# jlink_to_tag.net
KiCad netlist of a schematic drawn in EAGLE
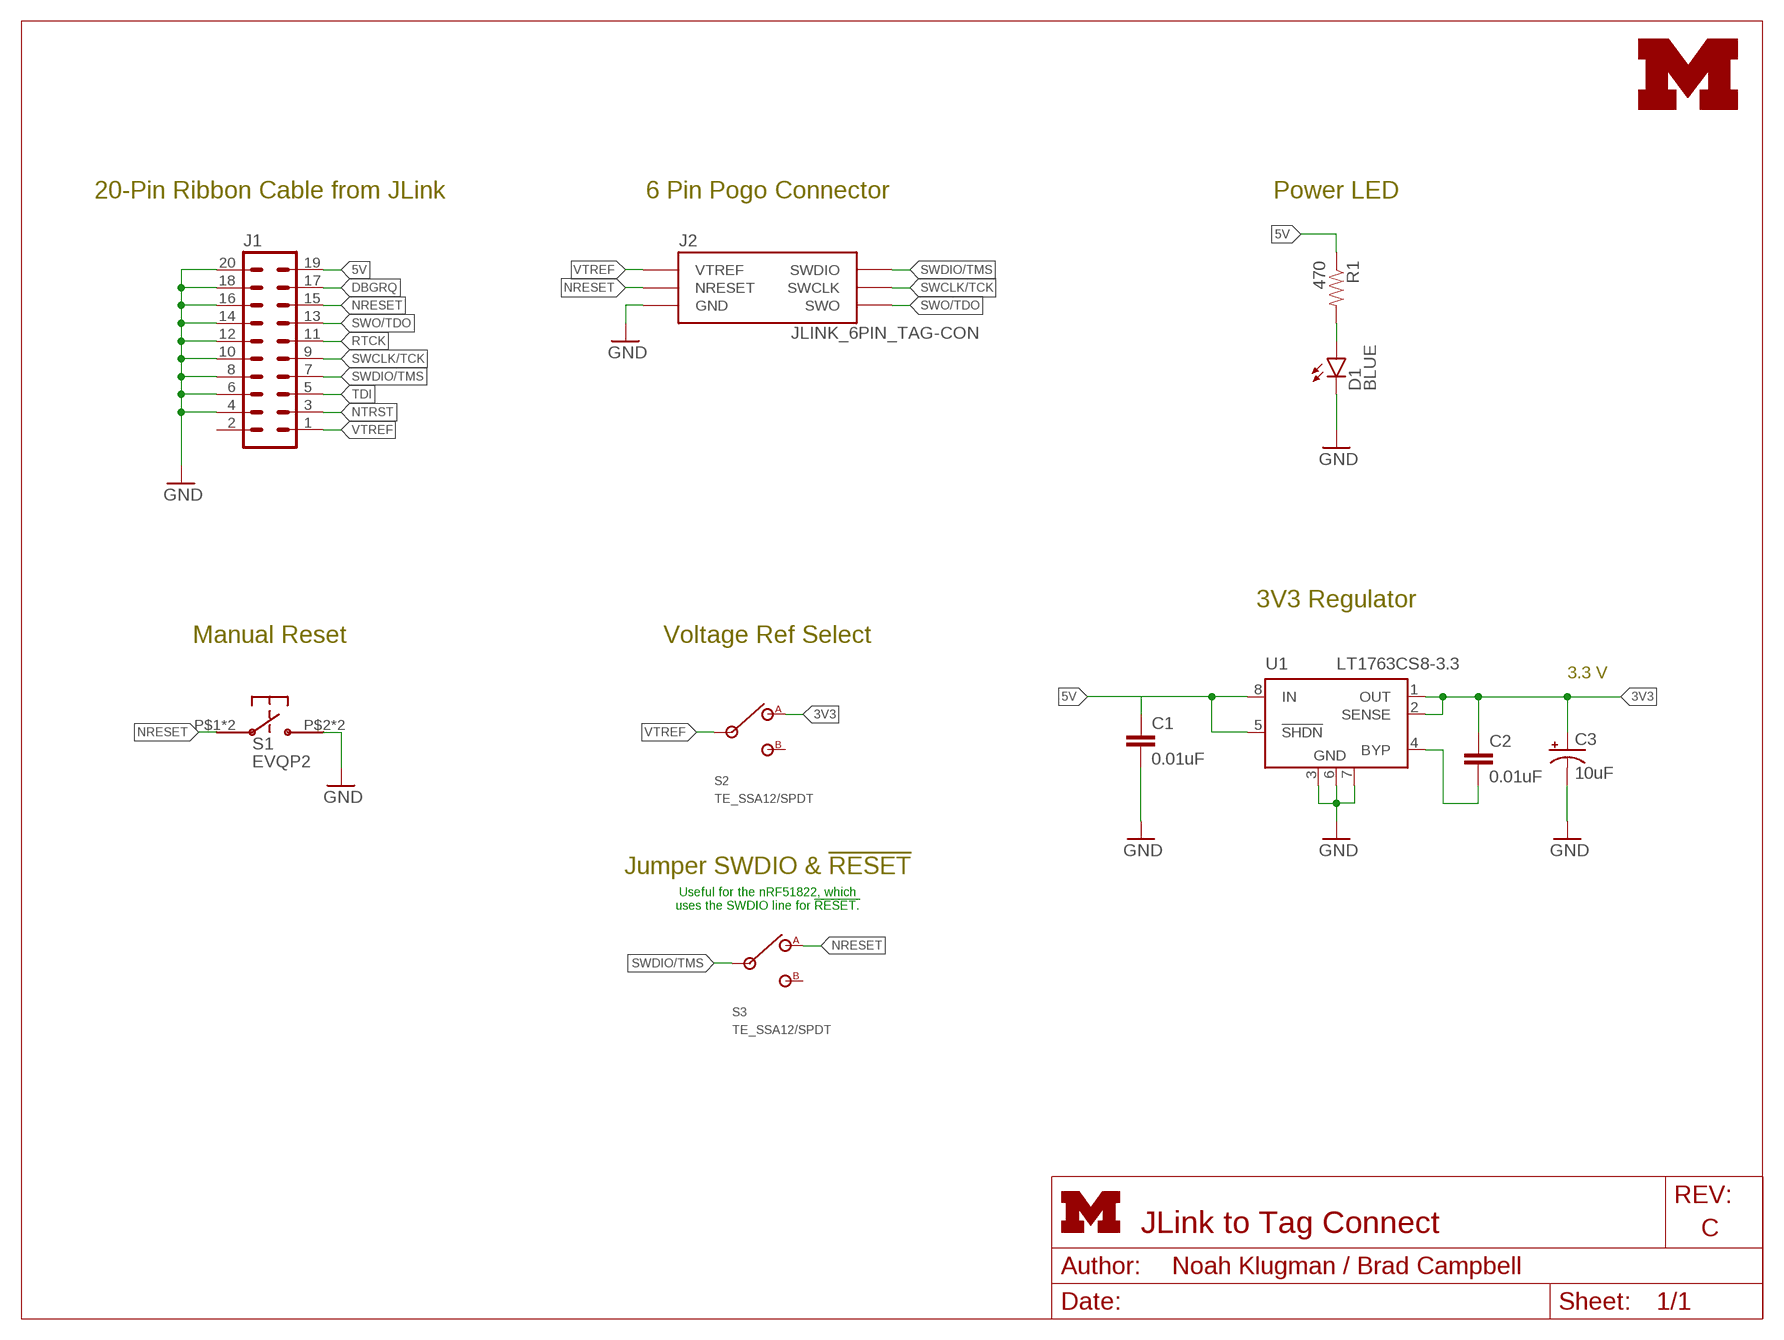
[diagram p0: schematic, sheet 1]

(export (version "E")
  (design (tool "Eeschema 10.0.6"))
  (components
    (comp (ref "C1")
      (value "0.01uF")
      (footprint "eagle-import:C0603")
      (libsource (lib "eagle-import") (part "C-EUC0603"))
    )
    (comp (ref "C2")
      (value "0.01uF")
      (footprint "eagle-import:C0603")
      (libsource (lib "eagle-import") (part "C-EUC0603"))
    )
    (comp (ref "C3")
      (value "10uF")
      (footprint "eagle-import:EIA3216")
      (libsource (lib "eagle-import") (part "CAP_POL1206"))
    )
    (comp (ref "D1")
      (value "BLUE")
      (footprint "eagle-import:LED-0603")
      (libsource (lib "eagle-import") (part "LED-BLUE0603"))
    )
    (comp (ref "J1")
      (value "ML20")
      (footprint "eagle-import:ML20")
      (libsource (lib "eagle-import") (part "ML20"))
    )
    (comp (ref "J2")
      (value "JLINK_6PIN_TAG-CON")
      (footprint "eagle-import:2X3_MALE_SHROUDED_0.100")
      (libsource (lib "eagle-import") (part "JLINK_6PIN_TAG-CON"))
    )
    (comp (ref "LOGO1")
      (value "UMICH_SOLID_SMALL+")
      (footprint "eagle-import:UMICH_SOLID_100MIL")
      (libsource (lib "eagle-import") (part "UMICH_SOLID_SMALL+"))
    )
    (comp (ref "R1")
      (value "470")
      (footprint "eagle-import:0603-RES")
      (libsource (lib "eagle-import") (part "RESISTOR0603-RES"))
    )
    (comp (ref "S1")
      (value "EVQP2")
      (footprint "eagle-import:EVQP2")
      (libsource (lib "eagle-import") (part "EVQP2"))
    )
    (comp (ref "S2")
      (value "TE_SSA12/SPDT")
      (footprint "eagle-import:TE_SSA12_SPDT")
      (libsource (lib "eagle-import") (part "TE_SSA12/SPDT"))
    )
    (comp (ref "S3")
      (value "TE_SSA12/SPDT")
      (footprint "eagle-import:TE_SSA12_SPDT")
      (libsource (lib "eagle-import") (part "TE_SSA12/SPDT"))
    )
    (comp (ref "U1")
      (value "LT1763CS8-3.3")
      (footprint "eagle-import:SOIC8")
      (libsource (lib "eagle-import") (part "LT1763CS8-3.3"))
    )
  )
  (nets
    (net (code "1") (name "3V3") (class "Default")
      (node (ref "C2") (pin "1") (pinfunction "1_1") (pintype "passive"))
      (node (ref "C3") (pin "A") (pinfunction "+_A") (pintype "passive"))
      (node (ref "S2") (pin "1") (pinfunction "A_1") (pintype "bidirectional"))
      (node (ref "U1") (pin "1") (pinfunction "OUT_1") (pintype "passive"))
      (node (ref "U1") (pin "2") (pinfunction "SENSE_2") (pintype "input"))
    )
    (net (code "2") (name "5V") (class "Default")
      (node (ref "C1") (pin "1") (pinfunction "1_1") (pintype "passive"))
      (node (ref "J1") (pin "19") (pinfunction "19_19") (pintype "passive"))
      (node (ref "R1") (pin "1") (pinfunction "1_1") (pintype "passive"))
      (node (ref "U1") (pin "5") (pinfunction "~{SHDN}_5") (pintype "input"))
      (node (ref "U1") (pin "8") (pinfunction "IN_8") (pintype "input"))
    )
    (net (code "3") (name "DBGRQ") (class "Default")
      (node (ref "J1") (pin "17") (pinfunction "17_17") (pintype "passive"))
    )
    (net (code "4") (name "GND") (class "Default")
      (node (ref "C1") (pin "2") (pinfunction "2_2") (pintype "passive"))
      (node (ref "C3") (pin "C") (pinfunction "-_C") (pintype "passive"))
      (node (ref "D1") (pin "C") (pinfunction "C_C") (pintype "passive"))
      (node (ref "J1") (pin "10") (pinfunction "10_10") (pintype "passive"))
      (node (ref "J1") (pin "12") (pinfunction "12_12") (pintype "passive"))
      (node (ref "J1") (pin "14") (pinfunction "14_14") (pintype "passive"))
      (node (ref "J1") (pin "16") (pinfunction "16_16") (pintype "passive"))
      (node (ref "J1") (pin "18") (pinfunction "18_18") (pintype "passive"))
      (node (ref "J1") (pin "20") (pinfunction "20_20") (pintype "passive"))
      (node (ref "J1") (pin "4") (pinfunction "4_4") (pintype "passive"))
      (node (ref "J1") (pin "6") (pinfunction "6_6") (pintype "passive"))
      (node (ref "J1") (pin "8") (pinfunction "8_8") (pintype "passive"))
      (node (ref "J2") (pin "5") (pinfunction "GND_5") (pintype "bidirectional"))
      (node (ref "S1") (pin "P$2") (pinfunction "P$2_P$2") (pintype "passive"))
      (node (ref "S1") (pin "P$4") (pinfunction "P$2_P$4") (pintype "passive"))
      (node (ref "U1") (pin "3") (pinfunction "GND_3") (pintype "power_in"))
      (node (ref "U1") (pin "6") (pinfunction "GND_6") (pintype "power_in"))
      (node (ref "U1") (pin "7") (pinfunction "GND_7") (pintype "power_in"))
    )
    (net (code "5") (name "NRESET") (class "Default")
      (node (ref "J1") (pin "15") (pinfunction "15_15") (pintype "passive"))
      (node (ref "J2") (pin "3") (pinfunction "NRESET_3") (pintype "bidirectional"))
      (node (ref "S1") (pin "P$1") (pinfunction "P$1_P$1") (pintype "passive"))
      (node (ref "S1") (pin "P$3") (pinfunction "P$1_P$3") (pintype "passive"))
      (node (ref "S3") (pin "1") (pinfunction "A_1") (pintype "bidirectional"))
    )
    (net (code "6") (name "NTRST") (class "Default")
      (node (ref "J1") (pin "3") (pinfunction "3_3") (pintype "passive"))
    )
    (net (code "7") (name "Net-(D1-PadA)") (class "Default")
      (node (ref "D1") (pin "A") (pinfunction "A_A") (pintype "passive"))
      (node (ref "R1") (pin "2") (pinfunction "2_2") (pintype "passive"))
    )
    (net (code "8") (name "Net-(U1-BYP)") (class "Default")
      (node (ref "C2") (pin "2") (pinfunction "2_2") (pintype "passive"))
      (node (ref "U1") (pin "4") (pinfunction "BYP_4") (pintype "input"))
    )
    (net (code "9") (name "RTCK") (class "Default")
      (node (ref "J1") (pin "11") (pinfunction "11_11") (pintype "passive"))
    )
    (net (code "10") (name "SWCLK{slash}TCK") (class "Default")
      (node (ref "J1") (pin "9") (pinfunction "9_9") (pintype "passive"))
      (node (ref "J2") (pin "4") (pinfunction "SWCLK_4") (pintype "bidirectional"))
    )
    (net (code "11") (name "SWDIO{slash}TMS") (class "Default")
      (node (ref "J1") (pin "7") (pinfunction "7_7") (pintype "passive"))
      (node (ref "J2") (pin "2") (pinfunction "SWDIO_2") (pintype "bidirectional"))
      (node (ref "S3") (pin "IN") (pinfunction "IN_IN") (pintype "bidirectional"))
    )
    (net (code "12") (name "SWO{slash}TDO") (class "Default")
      (node (ref "J1") (pin "13") (pinfunction "13_13") (pintype "passive"))
      (node (ref "J2") (pin "6") (pinfunction "SWO_6") (pintype "bidirectional"))
    )
    (net (code "13") (name "TDI") (class "Default")
      (node (ref "J1") (pin "5") (pinfunction "5_5") (pintype "passive"))
    )
    (net (code "14") (name "VTREF") (class "Default")
      (node (ref "J1") (pin "1") (pinfunction "1_1") (pintype "passive"))
      (node (ref "J2") (pin "1") (pinfunction "VTREF_1") (pintype "bidirectional"))
      (node (ref "S2") (pin "IN") (pinfunction "IN_IN") (pintype "bidirectional"))
    )
    (net (code "15") (name "unconnected-(J1-Pad2)") (class "Default")
      (node (ref "J1") (pin "2") (pinfunction "2_2") (pintype "passive"))
    )
    (net (code "16") (name "unconnected-(S2-B-Pad2)") (class "Default")
      (node (ref "S2") (pin "2") (pinfunction "B_2") (pintype "bidirectional"))
    )
    (net (code "17") (name "unconnected-(S3-B-Pad2)") (class "Default")
      (node (ref "S3") (pin "2") (pinfunction "B_2") (pintype "bidirectional"))
    )
  )
)
